# smt-led-testing-mk-1_0.net
KiCad netlist of a schematic drawn in EAGLE
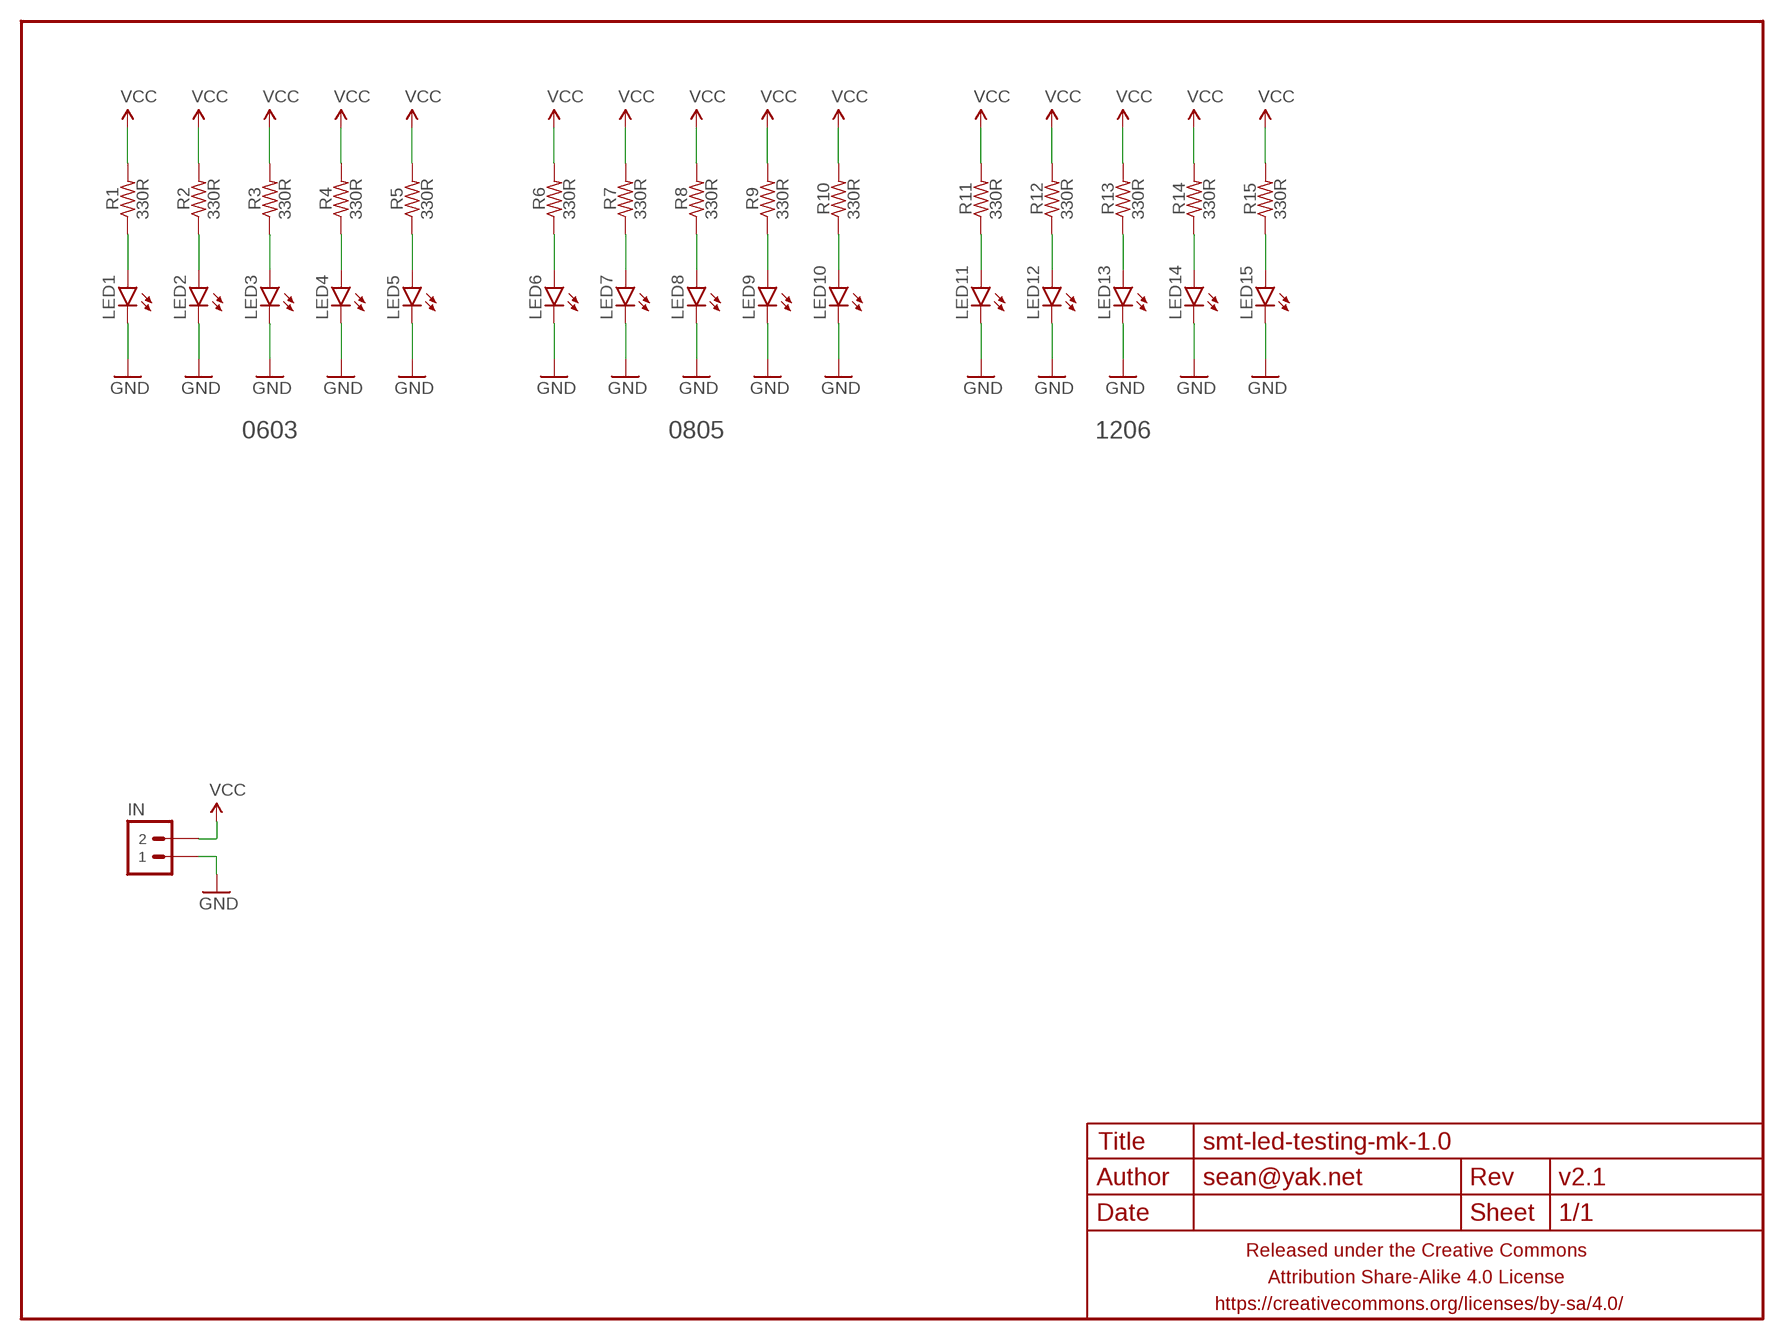
[diagram p0: schematic, sheet 1]

(export (version "E")
  (design (tool "Eeschema 10.0.6"))
  (components
    (comp (ref "FRAME1")
      (value "FRAME-LETTERNO_PACKAGE")
      (footprint "eagle-import:DUMMY")
      (fields (field (name "DESIGNER") "sean@yak.net") (field (name "VERSION") "v2.1"))
      (libsource (lib "eagle-import") (part "FRAME-LETTERNO_PACKAGE"))
    )
    (comp (ref "IN")
      (value "M02PTH-CENTERED-R+")
      (footprint "eagle-import:1X02-CENTER-R+")
      (libsource (lib "eagle-import") (part "M02PTH-CENTERED-R+"))
    )
    (comp (ref "LED1")
      (value "LED0603")
      (footprint "eagle-import:LED-0603")
      (libsource (lib "eagle-import") (part "LED0603"))
    )
    (comp (ref "LED2")
      (value "LED0603")
      (footprint "eagle-import:LED-0603")
      (libsource (lib "eagle-import") (part "LED0603"))
    )
    (comp (ref "LED3")
      (value "LED0603")
      (footprint "eagle-import:LED-0603")
      (libsource (lib "eagle-import") (part "LED0603"))
    )
    (comp (ref "LED4")
      (value "LED0603")
      (footprint "eagle-import:LED-0603")
      (libsource (lib "eagle-import") (part "LED0603"))
    )
    (comp (ref "LED5")
      (value "LED0603")
      (footprint "eagle-import:LED-0603")
      (libsource (lib "eagle-import") (part "LED0603"))
    )
    (comp (ref "LED6")
      (value "LED0805")
      (footprint "eagle-import:LED-0805")
      (libsource (lib "eagle-import") (part "LED0805"))
    )
    (comp (ref "LED7")
      (value "LED0805")
      (footprint "eagle-import:LED-0805")
      (libsource (lib "eagle-import") (part "LED0805"))
    )
    (comp (ref "LED8")
      (value "LED0805")
      (footprint "eagle-import:LED-0805")
      (libsource (lib "eagle-import") (part "LED0805"))
    )
    (comp (ref "LED9")
      (value "LED0805")
      (footprint "eagle-import:LED-0805")
      (libsource (lib "eagle-import") (part "LED0805"))
    )
    (comp (ref "LED10")
      (value "LED0805")
      (footprint "eagle-import:LED-0805")
      (libsource (lib "eagle-import") (part "LED0805"))
    )
    (comp (ref "LED11")
      (value "LED1206")
      (footprint "eagle-import:LED-1206")
      (libsource (lib "eagle-import") (part "LED1206"))
    )
    (comp (ref "LED12")
      (value "LED1206")
      (footprint "eagle-import:LED-1206")
      (libsource (lib "eagle-import") (part "LED1206"))
    )
    (comp (ref "LED13")
      (value "LED1206")
      (footprint "eagle-import:LED-1206")
      (libsource (lib "eagle-import") (part "LED1206"))
    )
    (comp (ref "LED14")
      (value "LED1206")
      (footprint "eagle-import:LED-1206")
      (libsource (lib "eagle-import") (part "LED1206"))
    )
    (comp (ref "LED15")
      (value "LED1206")
      (footprint "eagle-import:LED-1206")
      (libsource (lib "eagle-import") (part "LED1206"))
    )
    (comp (ref "R1")
      (value "330R")
      (footprint "eagle-import:R0603")
      (libsource (lib "eagle-import") (part "RESISTORR0603"))
    )
    (comp (ref "R2")
      (value "330R")
      (footprint "eagle-import:R0603")
      (libsource (lib "eagle-import") (part "RESISTORR0603"))
    )
    (comp (ref "R3")
      (value "330R")
      (footprint "eagle-import:R0603")
      (libsource (lib "eagle-import") (part "RESISTORR0603"))
    )
    (comp (ref "R4")
      (value "330R")
      (footprint "eagle-import:R0603")
      (libsource (lib "eagle-import") (part "RESISTORR0603"))
    )
    (comp (ref "R5")
      (value "330R")
      (footprint "eagle-import:R0603")
      (libsource (lib "eagle-import") (part "RESISTORR0603"))
    )
    (comp (ref "R6")
      (value "330R")
      (footprint "eagle-import:R0603")
      (libsource (lib "eagle-import") (part "RESISTORR0603"))
    )
    (comp (ref "R7")
      (value "330R")
      (footprint "eagle-import:R0603")
      (libsource (lib "eagle-import") (part "RESISTORR0603"))
    )
    (comp (ref "R8")
      (value "330R")
      (footprint "eagle-import:R0603")
      (libsource (lib "eagle-import") (part "RESISTORR0603"))
    )
    (comp (ref "R9")
      (value "330R")
      (footprint "eagle-import:R0603")
      (libsource (lib "eagle-import") (part "RESISTORR0603"))
    )
    (comp (ref "R10")
      (value "330R")
      (footprint "eagle-import:R0603")
      (libsource (lib "eagle-import") (part "RESISTORR0603"))
    )
    (comp (ref "R11")
      (value "330R")
      (footprint "eagle-import:R0603")
      (libsource (lib "eagle-import") (part "RESISTORR0603"))
    )
    (comp (ref "R12")
      (value "330R")
      (footprint "eagle-import:R0603")
      (libsource (lib "eagle-import") (part "RESISTORR0603"))
    )
    (comp (ref "R13")
      (value "330R")
      (footprint "eagle-import:R0603")
      (libsource (lib "eagle-import") (part "RESISTORR0603"))
    )
    (comp (ref "R14")
      (value "330R")
      (footprint "eagle-import:R0603")
      (libsource (lib "eagle-import") (part "RESISTORR0603"))
    )
    (comp (ref "R15")
      (value "330R")
      (footprint "eagle-import:R0603")
      (libsource (lib "eagle-import") (part "RESISTORR0603"))
    )
  )
  (nets
    (net (code "1") (name "GND") (class "Default")
      (node (ref "IN") (pin "1") (pinfunction "1_1") (pintype "passive"))
      (node (ref "LED1") (pin "C") (pinfunction "C_C") (pintype "passive"))
      (node (ref "LED10") (pin "C") (pinfunction "C_C") (pintype "passive"))
      (node (ref "LED11") (pin "C") (pinfunction "C_C") (pintype "passive"))
      (node (ref "LED12") (pin "C") (pinfunction "C_C") (pintype "passive"))
      (node (ref "LED13") (pin "C") (pinfunction "C_C") (pintype "passive"))
      (node (ref "LED14") (pin "C") (pinfunction "C_C") (pintype "passive"))
      (node (ref "LED15") (pin "C") (pinfunction "C_C") (pintype "passive"))
      (node (ref "LED2") (pin "C") (pinfunction "C_C") (pintype "passive"))
      (node (ref "LED3") (pin "C") (pinfunction "C_C") (pintype "passive"))
      (node (ref "LED4") (pin "C") (pinfunction "C_C") (pintype "passive"))
      (node (ref "LED5") (pin "C") (pinfunction "C_C") (pintype "passive"))
      (node (ref "LED6") (pin "C") (pinfunction "C_C") (pintype "passive"))
      (node (ref "LED7") (pin "C") (pinfunction "C_C") (pintype "passive"))
      (node (ref "LED8") (pin "C") (pinfunction "C_C") (pintype "passive"))
      (node (ref "LED9") (pin "C") (pinfunction "C_C") (pintype "passive"))
    )
    (net (code "2") (name "Net-(LED1-PadA)") (class "Default")
      (node (ref "LED1") (pin "A") (pinfunction "A_A") (pintype "passive"))
      (node (ref "R1") (pin "1") (pinfunction "1_1") (pintype "passive"))
    )
    (net (code "3") (name "Net-(LED2-PadA)") (class "Default")
      (node (ref "LED2") (pin "A") (pinfunction "A_A") (pintype "passive"))
      (node (ref "R2") (pin "1") (pinfunction "1_1") (pintype "passive"))
    )
    (net (code "4") (name "Net-(LED3-PadA)") (class "Default")
      (node (ref "LED3") (pin "A") (pinfunction "A_A") (pintype "passive"))
      (node (ref "R3") (pin "1") (pinfunction "1_1") (pintype "passive"))
    )
    (net (code "5") (name "Net-(LED4-PadA)") (class "Default")
      (node (ref "LED4") (pin "A") (pinfunction "A_A") (pintype "passive"))
      (node (ref "R4") (pin "1") (pinfunction "1_1") (pintype "passive"))
    )
    (net (code "6") (name "Net-(LED5-PadA)") (class "Default")
      (node (ref "LED5") (pin "A") (pinfunction "A_A") (pintype "passive"))
      (node (ref "R5") (pin "1") (pinfunction "1_1") (pintype "passive"))
    )
    (net (code "7") (name "Net-(LED6-PadA)") (class "Default")
      (node (ref "LED6") (pin "A") (pinfunction "A_A") (pintype "passive"))
      (node (ref "R6") (pin "1") (pinfunction "1_1") (pintype "passive"))
    )
    (net (code "8") (name "Net-(LED7-PadA)") (class "Default")
      (node (ref "LED7") (pin "A") (pinfunction "A_A") (pintype "passive"))
      (node (ref "R7") (pin "1") (pinfunction "1_1") (pintype "passive"))
    )
    (net (code "9") (name "Net-(LED8-PadA)") (class "Default")
      (node (ref "LED8") (pin "A") (pinfunction "A_A") (pintype "passive"))
      (node (ref "R8") (pin "1") (pinfunction "1_1") (pintype "passive"))
    )
    (net (code "10") (name "Net-(LED9-PadA)") (class "Default")
      (node (ref "LED9") (pin "A") (pinfunction "A_A") (pintype "passive"))
      (node (ref "R9") (pin "1") (pinfunction "1_1") (pintype "passive"))
    )
    (net (code "11") (name "Net-(LED10-PadA)") (class "Default")
      (node (ref "LED10") (pin "A") (pinfunction "A_A") (pintype "passive"))
      (node (ref "R10") (pin "1") (pinfunction "1_1") (pintype "passive"))
    )
    (net (code "12") (name "Net-(LED11-PadA)") (class "Default")
      (node (ref "LED11") (pin "A") (pinfunction "A_A") (pintype "passive"))
      (node (ref "R11") (pin "1") (pinfunction "1_1") (pintype "passive"))
    )
    (net (code "13") (name "Net-(LED12-PadA)") (class "Default")
      (node (ref "LED12") (pin "A") (pinfunction "A_A") (pintype "passive"))
      (node (ref "R12") (pin "1") (pinfunction "1_1") (pintype "passive"))
    )
    (net (code "14") (name "Net-(LED13-PadA)") (class "Default")
      (node (ref "LED13") (pin "A") (pinfunction "A_A") (pintype "passive"))
      (node (ref "R13") (pin "1") (pinfunction "1_1") (pintype "passive"))
    )
    (net (code "15") (name "Net-(LED14-PadA)") (class "Default")
      (node (ref "LED14") (pin "A") (pinfunction "A_A") (pintype "passive"))
      (node (ref "R14") (pin "1") (pinfunction "1_1") (pintype "passive"))
    )
    (net (code "16") (name "Net-(LED15-PadA)") (class "Default")
      (node (ref "LED15") (pin "A") (pinfunction "A_A") (pintype "passive"))
      (node (ref "R15") (pin "1") (pinfunction "1_1") (pintype "passive"))
    )
    (net (code "17") (name "VCC") (class "Default")
      (node (ref "IN") (pin "2") (pinfunction "2_2") (pintype "passive"))
      (node (ref "R1") (pin "2") (pinfunction "2_2") (pintype "passive"))
      (node (ref "R10") (pin "2") (pinfunction "2_2") (pintype "passive"))
      (node (ref "R11") (pin "2") (pinfunction "2_2") (pintype "passive"))
      (node (ref "R12") (pin "2") (pinfunction "2_2") (pintype "passive"))
      (node (ref "R13") (pin "2") (pinfunction "2_2") (pintype "passive"))
      (node (ref "R14") (pin "2") (pinfunction "2_2") (pintype "passive"))
      (node (ref "R15") (pin "2") (pinfunction "2_2") (pintype "passive"))
      (node (ref "R2") (pin "2") (pinfunction "2_2") (pintype "passive"))
      (node (ref "R3") (pin "2") (pinfunction "2_2") (pintype "passive"))
      (node (ref "R4") (pin "2") (pinfunction "2_2") (pintype "passive"))
      (node (ref "R5") (pin "2") (pinfunction "2_2") (pintype "passive"))
      (node (ref "R6") (pin "2") (pinfunction "2_2") (pintype "passive"))
      (node (ref "R7") (pin "2") (pinfunction "2_2") (pintype "passive"))
      (node (ref "R8") (pin "2") (pinfunction "2_2") (pintype "passive"))
      (node (ref "R9") (pin "2") (pinfunction "2_2") (pintype "passive"))
    )
  )
)
